# Sheet2.net
KiCad netlist of a schematic drawn in Altium Designer
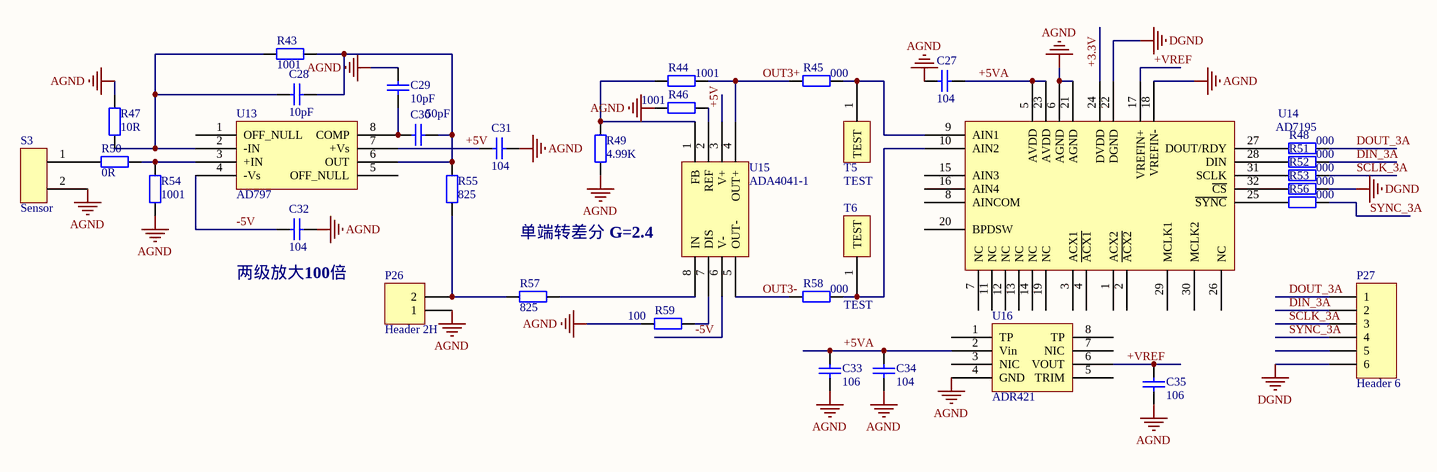
[diagram p0: Sheet2.SchDoc]

(export (version "E")
  (design (tool "Eeschema 10.0.6"))
  (components
    (comp (ref "C27")
      (value "104")
      (footprint "0805C")
      (description "Capacitor")
      (fields (field (name "PUBLISHER") "Altium Limited"))
      (libsource (lib "Miscellaneous Devices") (part "Cap"))
    )
    (comp (ref "C28")
      (value "10pF")
      (footprint "0805C")
      (description "Capacitor")
      (fields (field (name "PUBLISHER") "Altium Limited"))
      (libsource (lib "Miscellaneous Devices") (part "Cap"))
    )
    (comp (ref "C29")
      (value "10pF")
      (footprint "0805C")
      (description "Capacitor")
      (fields (field (name "PUBLISHER") "Altium Limited"))
      (libsource (lib "Miscellaneous Devices") (part "Cap"))
    )
    (comp (ref "C30")
      (value "50pF")
      (footprint "0805C")
      (description "Capacitor")
      (fields (field (name "PUBLISHER") "Altium Limited"))
      (libsource (lib "Miscellaneous Devices") (part "Cap"))
    )
    (comp (ref "C31")
      (value "104")
      (footprint "0805C")
      (description "Capacitor")
      (fields (field (name "PUBLISHER") "Altium Limited"))
      (libsource (lib "Miscellaneous Devices") (part "Cap"))
    )
    (comp (ref "C32")
      (value "104")
      (footprint "0805C")
      (description "Capacitor")
      (fields (field (name "PUBLISHER") "Altium Limited"))
      (libsource (lib "Miscellaneous Devices") (part "Cap"))
    )
    (comp (ref "C33")
      (value "106")
      (footprint "0805C")
      (description "Capacitor")
      (fields (field (name "PUBLISHER") "Altium Limited"))
      (libsource (lib "Miscellaneous Devices") (part "Cap"))
    )
    (comp (ref "C34")
      (value "104")
      (footprint "0805C")
      (description "Capacitor")
      (fields (field (name "PUBLISHER") "Altium Limited"))
      (libsource (lib "Miscellaneous Devices") (part "Cap"))
    )
    (comp (ref "C35")
      (value "106")
      (footprint "0805C")
      (description "Capacitor")
      (fields (field (name "PUBLISHER") "Altium Limited"))
      (libsource (lib "Miscellaneous Devices") (part "Cap"))
    )
    (comp (ref "P26")
      (value "Header 2H")
      (footprint "HDR1X2")
      (description "Header, 2-Pin, Right Angle")
      (fields (field (name "PUBLISHER") "Altium Limited"))
      (libsource (lib "Miscellaneous Connectors") (part "Header 2H"))
    )
    (comp (ref "P27")
      (value "Header 6")
      (footprint "HDR1X6")
      (description "Header, 6-Pin")
      (fields (field (name "PUBLISHER") "Altium Limited"))
      (libsource (lib "Miscellaneous Connectors") (part "Header 6"))
    )
    (comp (ref "R43")
      (value "1001")
      (footprint "0805R")
      (description "Resistor")
      (fields (field (name "PUBLISHER") "Altium Limited"))
      (libsource (lib "Miscellaneous Devices") (part "Res2"))
    )
    (comp (ref "R44")
      (value "1001")
      (footprint "0805R")
      (description "Resistor")
      (fields (field (name "PUBLISHER") "Altium Limited"))
      (libsource (lib "Miscellaneous Devices") (part "Res2"))
    )
    (comp (ref "R45")
      (value "000")
      (footprint "0805R")
      (description "Resistor")
      (fields (field (name "PUBLISHER") "Altium Limited"))
      (libsource (lib "Miscellaneous Devices") (part "Res2"))
    )
    (comp (ref "R46")
      (value "1001")
      (footprint "0805R")
      (description "Resistor")
      (fields (field (name "PUBLISHER") "Altium Limited"))
      (libsource (lib "Miscellaneous Devices") (part "Res2"))
    )
    (comp (ref "R47")
      (value "10R")
      (footprint "0805R")
      (description "Resistor")
      (fields (field (name "PUBLISHER") "Altium Limited"))
      (libsource (lib "") (part "Res2_2"))
    )
    (comp (ref "R48")
      (value "000")
      (footprint "0805R")
      (description "Resistor")
      (fields (field (name "PUBLISHER") "Altium Limited"))
      (libsource (lib "Miscellaneous Devices") (part "Res2"))
    )
    (comp (ref "R49")
      (value "4.99K")
      (footprint "0805R")
      (description "Resistor")
      (fields (field (name "PUBLISHER") "Altium Limited"))
      (libsource (lib "") (part "Res2_1"))
    )
    (comp (ref "R50")
      (value "0R")
      (footprint "0805R")
      (description "Resistor")
      (fields (field (name "PUBLISHER") "Altium Limited"))
      (libsource (lib "Miscellaneous Devices") (part "Res2"))
    )
    (comp (ref "R51")
      (value "000")
      (footprint "0805R")
      (description "Resistor")
      (fields (field (name "PUBLISHER") "Altium Limited"))
      (libsource (lib "Miscellaneous Devices") (part "Res2"))
    )
    (comp (ref "R52")
      (value "000")
      (footprint "0805R")
      (description "Resistor")
      (fields (field (name "PUBLISHER") "Altium Limited"))
      (libsource (lib "Miscellaneous Devices") (part "Res2"))
    )
    (comp (ref "R53")
      (value "000")
      (footprint "0805R")
      (description "Resistor")
      (fields (field (name "PUBLISHER") "Altium Limited"))
      (libsource (lib "Miscellaneous Devices") (part "Res2"))
    )
    (comp (ref "R54")
      (value "1001")
      (footprint "0805R")
      (description "Resistor")
      (fields (field (name "PUBLISHER") "Altium Limited"))
      (libsource (lib "") (part "Res2_1"))
    )
    (comp (ref "R55")
      (value "825")
      (footprint "0805R")
      (description "Resistor")
      (fields (field (name "PUBLISHER") "Altium Limited"))
      (libsource (lib "") (part "Res2_1"))
    )
    (comp (ref "R56")
      (value "000")
      (footprint "0805R")
      (description "Resistor")
      (fields (field (name "PUBLISHER") "Altium Limited"))
      (libsource (lib "Miscellaneous Devices") (part "Res2"))
    )
    (comp (ref "R57")
      (value "825")
      (footprint "0805R")
      (description "Resistor")
      (fields (field (name "PUBLISHER") "Altium Limited"))
      (libsource (lib "Miscellaneous Devices") (part "Res2"))
    )
    (comp (ref "R58")
      (value "000")
      (footprint "0805R")
      (description "Resistor")
      (fields (field (name "PUBLISHER") "Altium Limited"))
      (libsource (lib "Miscellaneous Devices") (part "Res2"))
    )
    (comp (ref "R59")
      (value "100")
      (footprint "0805R")
      (description "Resistor")
      (fields (field (name "PUBLISHER") "Altium Limited"))
      (libsource (lib "Miscellaneous Devices") (part "Res2"))
    )
    (comp (ref "S3") (value "Sensor") (footprint "HDR1X2") (libsource (lib "Schlib1") (part "Sensor")))
    (comp (ref "T5") (value "TEST") (footprint "TEST") (libsource (lib "Schlib1") (part "TEST")))
    (comp (ref "T6") (value "TEST") (footprint "TEST") (libsource (lib "") (part "TEST_1")))
    (comp (ref "U13") (value "AD797") (footprint "SO8") (libsource (lib "Schlib1") (part "AD797")))
    (comp (ref "U14") (value "AD7195") (footprint "LFCSP32") (libsource (lib "Schlib1") (part "AD7195")))
    (comp (ref "U15") (value "ADA4041-1") (footprint "SO8") (libsource (lib "Schlib1") (part "ADA4041-1")))
    (comp (ref "U16") (value "ADR421") (footprint "SO8") (libsource (lib "Schlib1") (part "ADR421")))
  )
  (nets
    (net (code "1") (name "/+3.3V") (class "Default")
      (node (ref "U14") (pin "24") (pinfunction "DVDD_24") (pintype "passive"))
    )
    (net (code "2") (name "/+5V") (class "Default")
      (node (ref "C31") (pin "2") (pinfunction "2_2") (pintype "passive"))
      (node (ref "U13") (pin "7") (pinfunction "+Vs_7") (pintype "passive"))
      (node (ref "U15") (pin "3") (pinfunction "V+_3") (pintype "passive"))
    )
    (net (code "3") (name "/+5VA") (class "Default")
      (node (ref "C27") (pin "2") (pinfunction "2_2") (pintype "passive"))
      (node (ref "C33") (pin "1") (pinfunction "1_1") (pintype "passive"))
      (node (ref "C34") (pin "1") (pinfunction "1_1") (pintype "passive"))
      (node (ref "U14") (pin "23") (pinfunction "AVDD_23") (pintype "passive"))
      (node (ref "U14") (pin "5") (pinfunction "AVDD_5") (pintype "passive"))
      (node (ref "U16") (pin "2") (pinfunction "Vin_2") (pintype "passive"))
    )
    (net (code "4") (name "/+VREF") (class "Default")
      (node (ref "C35") (pin "1") (pinfunction "1_1") (pintype "passive"))
      (node (ref "U14") (pin "17") (pinfunction "VREFIN+_17") (pintype "passive"))
      (node (ref "U16") (pin "6") (pinfunction "VOUT_6") (pintype "passive"))
    )
    (net (code "5") (name "/-5V") (class "Default")
      (node (ref "C32") (pin "2") (pinfunction "2_2") (pintype "passive"))
      (node (ref "U13") (pin "4") (pinfunction "-Vs_4") (pintype "passive"))
      (node (ref "U15") (pin "6") (pinfunction "V-_6") (pintype "passive"))
    )
    (net (code "6") (name "/DIN_3A") (class "Default")
      (node (ref "P27") (pin "2") (pinfunction "2_2") (pintype "passive"))
      (node (ref "R51") (pin "2") (pinfunction "2_2") (pintype "passive"))
    )
    (net (code "7") (name "/DOUT_3A") (class "Default")
      (node (ref "P27") (pin "1") (pinfunction "1_1") (pintype "passive"))
      (node (ref "R48") (pin "2") (pinfunction "2_2") (pintype "passive"))
    )
    (net (code "8") (name "/OUT3+") (class "Default")
      (node (ref "R44") (pin "2") (pinfunction "2_2") (pintype "passive"))
      (node (ref "R45") (pin "1") (pinfunction "1_1") (pintype "passive"))
      (node (ref "U15") (pin "4") (pinfunction "OUT+_4") (pintype "passive"))
    )
    (net (code "9") (name "/OUT3-") (class "Default")
      (node (ref "R58") (pin "1") (pinfunction "1_1") (pintype "passive"))
      (node (ref "U15") (pin "5") (pinfunction "OUT-_5") (pintype "passive"))
    )
    (net (code "10") (name "/SCLK_3A") (class "Default")
      (node (ref "P27") (pin "3") (pinfunction "3_3") (pintype "passive"))
      (node (ref "R52") (pin "2") (pinfunction "2_2") (pintype "passive"))
    )
    (net (code "11") (name "/SYNC_3A") (class "Default")
      (node (ref "P27") (pin "4") (pinfunction "4_4") (pintype "passive"))
      (node (ref "R56") (pin "2") (pinfunction "2_2") (pintype "passive"))
    )
    (net (code "12") (name "AGND") (class "Default")
      (node (ref "C27") (pin "1") (pinfunction "1_1") (pintype "passive"))
      (node (ref "C29") (pin "2") (pinfunction "2_2") (pintype "passive"))
      (node (ref "C31") (pin "1") (pinfunction "1_1") (pintype "passive"))
      (node (ref "C32") (pin "1") (pinfunction "1_1") (pintype "passive"))
      (node (ref "C33") (pin "2") (pinfunction "2_2") (pintype "passive"))
      (node (ref "C34") (pin "2") (pinfunction "2_2") (pintype "passive"))
      (node (ref "C35") (pin "2") (pinfunction "2_2") (pintype "passive"))
      (node (ref "P26") (pin "1") (pinfunction "1_1") (pintype "passive"))
      (node (ref "R46") (pin "1") (pinfunction "1_1") (pintype "passive"))
      (node (ref "R47") (pin "1") (pinfunction "1_1") (pintype "passive"))
      (node (ref "R49") (pin "1") (pinfunction "1_1") (pintype "passive"))
      (node (ref "R54") (pin "1") (pinfunction "1_1") (pintype "passive"))
      (node (ref "R59") (pin "1") (pinfunction "1_1") (pintype "passive"))
      (node (ref "S3") (pin "2") (pinfunction "2_2") (pintype "passive"))
      (node (ref "U14") (pin "18") (pinfunction "VREFIN-_18") (pintype "passive"))
      (node (ref "U14") (pin "21") (pinfunction "AGND_21") (pintype "passive"))
      (node (ref "U14") (pin "6") (pinfunction "AGND_6") (pintype "passive"))
      (node (ref "U16") (pin "4") (pinfunction "GND_4") (pintype "passive"))
    )
    (net (code "13") (name "DGND") (class "Default")
      (node (ref "P27") (pin "6") (pinfunction "6_6") (pintype "passive"))
      (node (ref "R53") (pin "2") (pinfunction "2_2") (pintype "passive"))
      (node (ref "U14") (pin "22") (pinfunction "DGND_22") (pintype "passive"))
    )
    (net (code "14") (name "Net-(P26-Pad2)") (class "Default")
      (node (ref "P26") (pin "2") (pinfunction "2_2") (pintype "passive"))
      (node (ref "R55") (pin "1") (pinfunction "1_1") (pintype "passive"))
      (node (ref "R57") (pin "1") (pinfunction "1_1") (pintype "passive"))
    )
    (net (code "15") (name "Net-(R50-Pad1)") (class "Default")
      (node (ref "R50") (pin "1") (pinfunction "1_1") (pintype "passive"))
      (node (ref "S3") (pin "1") (pinfunction "1_1") (pintype "passive"))
    )
    (net (code "16") (name "Net-(T5-TEST)") (class "Default")
      (node (ref "R45") (pin "2") (pinfunction "2_2") (pintype "passive"))
      (node (ref "T5") (pin "1") (pinfunction "TEST_1") (pintype "passive"))
      (node (ref "U14") (pin "9") (pinfunction "AIN1_9") (pintype "passive"))
    )
    (net (code "17") (name "Net-(T6-TEST)") (class "Default")
      (node (ref "R58") (pin "2") (pinfunction "2_2") (pintype "passive"))
      (node (ref "T6") (pin "1") (pinfunction "TEST_1") (pintype "passive"))
      (node (ref "U14") (pin "10") (pinfunction "AIN2_10") (pintype "passive"))
    )
    (net (code "18") (name "Net-(U13-+IN)") (class "Default")
      (node (ref "R50") (pin "2") (pinfunction "2_2") (pintype "passive"))
      (node (ref "R54") (pin "2") (pinfunction "2_2") (pintype "passive"))
      (node (ref "U13") (pin "3") (pinfunction "+IN_3") (pintype "passive"))
    )
    (net (code "19") (name "Net-(U13--IN)") (class "Default")
      (node (ref "C28") (pin "2") (pinfunction "2_2") (pintype "passive"))
      (node (ref "R43") (pin "1") (pinfunction "1_1") (pintype "passive"))
      (node (ref "R47") (pin "2") (pinfunction "2_2") (pintype "passive"))
      (node (ref "U13") (pin "2") (pinfunction "-IN_2") (pintype "passive"))
    )
    (net (code "20") (name "Net-(U13-COMP)") (class "Default")
      (node (ref "C29") (pin "1") (pinfunction "1_1") (pintype "passive"))
      (node (ref "C30") (pin "2") (pinfunction "2_2") (pintype "passive"))
      (node (ref "U13") (pin "8") (pinfunction "COMP_8") (pintype "passive"))
    )
    (net (code "21") (name "Net-(U13-OUT)") (class "Default")
      (node (ref "C28") (pin "1") (pinfunction "1_1") (pintype "passive"))
      (node (ref "C30") (pin "1") (pinfunction "1_1") (pintype "passive"))
      (node (ref "R43") (pin "2") (pinfunction "2_2") (pintype "passive"))
      (node (ref "R55") (pin "2") (pinfunction "2_2") (pintype "passive"))
      (node (ref "U13") (pin "6") (pinfunction "OUT_6") (pintype "passive"))
    )
    (net (code "22") (name "Net-(U14-DIN)") (class "Default")
      (node (ref "R51") (pin "1") (pinfunction "1_1") (pintype "passive"))
      (node (ref "U14") (pin "28") (pinfunction "DIN_28") (pintype "passive"))
    )
    (net (code "23") (name "Net-(U14-DOUT{slash}RDY)") (class "Default")
      (node (ref "R48") (pin "1") (pinfunction "1_1") (pintype "passive"))
      (node (ref "U14") (pin "27") (pinfunction "DOUT/RDY_27") (pintype "passive"))
    )
    (net (code "24") (name "Net-(U14-SCLK)") (class "Default")
      (node (ref "R52") (pin "1") (pinfunction "1_1") (pintype "passive"))
      (node (ref "U14") (pin "31") (pinfunction "SCLK_31") (pintype "passive"))
    )
    (net (code "25") (name "Net-(U14-~{CS})") (class "Default")
      (node (ref "R53") (pin "1") (pinfunction "1_1") (pintype "passive"))
      (node (ref "U14") (pin "32") (pinfunction "~{CS}_32") (pintype "passive"))
    )
    (net (code "26") (name "Net-(U14-~{SYNC})") (class "Default")
      (node (ref "R56") (pin "1") (pinfunction "1_1") (pintype "passive"))
      (node (ref "U14") (pin "25") (pinfunction "~{SYNC}_25") (pintype "passive"))
    )
    (net (code "27") (name "Net-(U15-DIS)") (class "Default")
      (node (ref "R59") (pin "2") (pinfunction "2_2") (pintype "passive"))
      (node (ref "U15") (pin "7") (pinfunction "DIS_7") (pintype "passive"))
    )
    (net (code "28") (name "Net-(U15-FB)") (class "Default")
      (node (ref "R44") (pin "1") (pinfunction "1_1") (pintype "passive"))
      (node (ref "R49") (pin "2") (pinfunction "2_2") (pintype "passive"))
      (node (ref "U15") (pin "1") (pinfunction "FB_1") (pintype "passive"))
    )
    (net (code "29") (name "Net-(U15-IN)") (class "Default")
      (node (ref "R57") (pin "2") (pinfunction "2_2") (pintype "passive"))
      (node (ref "U15") (pin "8") (pinfunction "IN_8") (pintype "passive"))
    )
    (net (code "30") (name "Net-(U15-REF)") (class "Default")
      (node (ref "R46") (pin "2") (pinfunction "2_2") (pintype "passive"))
      (node (ref "U15") (pin "2") (pinfunction "REF_2") (pintype "passive"))
    )
    (net (code "31") (name "unconnected-(P27-Pad5)") (class "Default")
      (node (ref "P27") (pin "5") (pinfunction "5_5") (pintype "passive"))
    )
    (net (code "32") (name "unconnected-(U13-OFF_NULL-Pad1)") (class "Default")
      (node (ref "U13") (pin "1") (pinfunction "OFF_NULL_1") (pintype "passive"))
    )
    (net (code "33") (name "unconnected-(U13-OFF_NULL-Pad5)") (class "Default")
      (node (ref "U13") (pin "5") (pinfunction "OFF_NULL_5") (pintype "passive"))
    )
    (net (code "34") (name "unconnected-(U14-ACX1-Pad3)") (class "Default")
      (node (ref "U14") (pin "3") (pinfunction "ACX1_3") (pintype "passive"))
    )
    (net (code "35") (name "unconnected-(U14-ACX2-Pad1)") (class "Default")
      (node (ref "U14") (pin "1") (pinfunction "ACX2_1") (pintype "passive"))
    )
    (net (code "36") (name "unconnected-(U14-AIN3-Pad15)") (class "Default")
      (node (ref "U14") (pin "15") (pinfunction "AIN3_15") (pintype "passive"))
    )
    (net (code "37") (name "unconnected-(U14-AIN4-Pad16)") (class "Default")
      (node (ref "U14") (pin "16") (pinfunction "AIN4_16") (pintype "passive"))
    )
    (net (code "38") (name "unconnected-(U14-AINCOM-Pad8)") (class "Default")
      (node (ref "U14") (pin "8") (pinfunction "AINCOM_8") (pintype "passive"))
    )
    (net (code "39") (name "unconnected-(U14-BPDSW-Pad20)") (class "Default")
      (node (ref "U14") (pin "20") (pinfunction "BPDSW_20") (pintype "passive"))
    )
    (net (code "40") (name "unconnected-(U14-MCLK1-Pad29)") (class "Default")
      (node (ref "U14") (pin "29") (pinfunction "MCLK1_29") (pintype "passive"))
    )
    (net (code "41") (name "unconnected-(U14-MCLK2-Pad30)") (class "Default")
      (node (ref "U14") (pin "30") (pinfunction "MCLK2_30") (pintype "passive"))
    )
    (net (code "42") (name "unconnected-(U14-NC-Pad7)") (class "Default")
      (node (ref "U14") (pin "7") (pinfunction "NC_7") (pintype "passive"))
    )
    (net (code "43") (name "unconnected-(U14-NC-Pad11)") (class "Default")
      (node (ref "U14") (pin "11") (pinfunction "NC_11") (pintype "passive"))
    )
    (net (code "44") (name "unconnected-(U14-NC-Pad12)") (class "Default")
      (node (ref "U14") (pin "12") (pinfunction "NC_12") (pintype "passive"))
    )
    (net (code "45") (name "unconnected-(U14-NC-Pad13)") (class "Default")
      (node (ref "U14") (pin "13") (pinfunction "NC_13") (pintype "passive"))
    )
    (net (code "46") (name "unconnected-(U14-NC-Pad14)") (class "Default")
      (node (ref "U14") (pin "14") (pinfunction "NC_14") (pintype "passive"))
    )
    (net (code "47") (name "unconnected-(U14-NC-Pad19)") (class "Default")
      (node (ref "U14") (pin "19") (pinfunction "NC_19") (pintype "passive"))
    )
    (net (code "48") (name "unconnected-(U14-NC-Pad26)") (class "Default")
      (node (ref "U14") (pin "26") (pinfunction "NC_26") (pintype "passive"))
    )
    (net (code "49") (name "unconnected-(U14-~{ACX1}-Pad4)") (class "Default")
      (node (ref "U14") (pin "4") (pinfunction "~{ACX1}_4") (pintype "passive"))
    )
    (net (code "50") (name "unconnected-(U14-~{ACX2}-Pad2)") (class "Default")
      (node (ref "U14") (pin "2") (pinfunction "~{ACX2}_2") (pintype "passive"))
    )
    (net (code "51") (name "unconnected-(U16-NIC-Pad3)") (class "Default")
      (node (ref "U16") (pin "3") (pinfunction "NIC_3") (pintype "passive"))
    )
    (net (code "52") (name "unconnected-(U16-NIC-Pad7)") (class "Default")
      (node (ref "U16") (pin "7") (pinfunction "NIC_7") (pintype "passive"))
    )
    (net (code "53") (name "unconnected-(U16-TP-Pad1)") (class "Default")
      (node (ref "U16") (pin "1") (pinfunction "TP_1") (pintype "passive"))
    )
    (net (code "54") (name "unconnected-(U16-TP-Pad8)") (class "Default")
      (node (ref "U16") (pin "8") (pinfunction "TP_8") (pintype "passive"))
    )
    (net (code "55") (name "unconnected-(U16-TRIM-Pad5)") (class "Default")
      (node (ref "U16") (pin "5") (pinfunction "TRIM_5") (pintype "passive"))
    )
  )
)
